# Pressure_Sensor_Platform.net
KiCad netlist of a schematic drawn in EAGLE
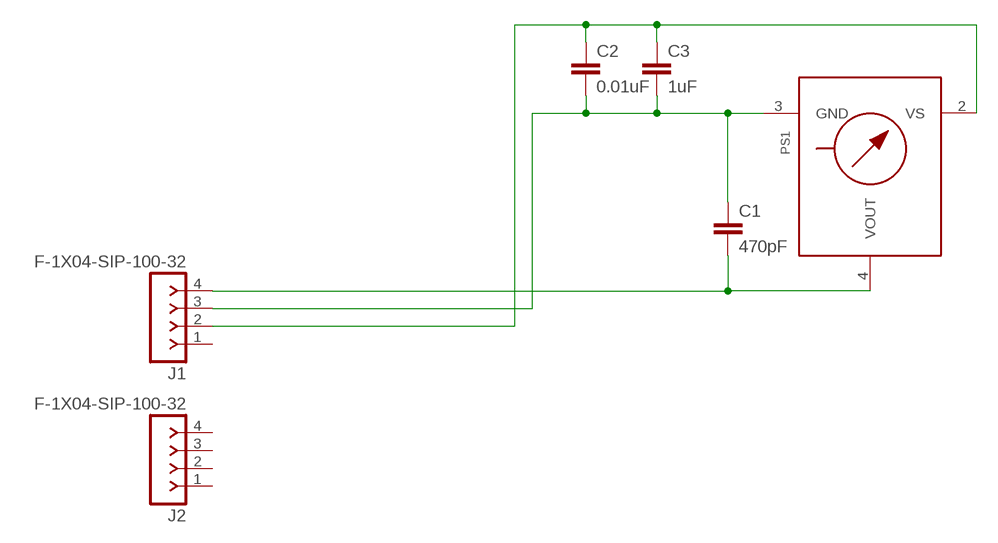
[diagram p0: schematic, sheet 1]

(export (version "E")
  (design (tool "Eeschema 10.0.6"))
  (components
    (comp (ref "C1")
      (value "470pF")
      (footprint "eagle-import:CAP-PTH-SMALL-KIT")
      (libsource (lib "eagle-import") (part "0.1UF-KIT-EZ-50V-20%"))
    )
    (comp (ref "C2")
      (value "0.01uF")
      (footprint "eagle-import:CAP-PTH-SMALL-KIT")
      (libsource (lib "eagle-import") (part "0.1UF-KIT-EZ-50V-20%"))
    )
    (comp (ref "C3")
      (value "1uF")
      (footprint "eagle-import:CAP-PTH-SMALL-KIT")
      (libsource (lib "eagle-import") (part "0.1UF-KIT-EZ-50V-20%"))
    )
    (comp (ref "J1")
      (value "F-1X04-SIP-100-32")
      (footprint "eagle-import:SIP-100-04-32")
      (libsource (lib "eagle-import") (part "F-1X04-SIP-100-32"))
    )
    (comp (ref "J2")
      (value "F-1X04-SIP-100-32")
      (footprint "eagle-import:SIP-100-04-32")
      (libsource (lib "eagle-import") (part "F-1X04-SIP-100-32"))
    )
    (comp (ref "PS1")
      (value "MPX-1351")
      (footprint "eagle-import:1351")
      (libsource (lib "eagle-import") (part "MPX-1351"))
    )
  )
  (nets
    (net (code "1") (name "Net-(PS1-GND)") (class "Default")
      (node (ref "C1") (pin "1") (pinfunction "1_1") (pintype "passive"))
      (node (ref "C2") (pin "2") (pinfunction "2_2") (pintype "passive"))
      (node (ref "C3") (pin "2") (pinfunction "2_2") (pintype "passive"))
      (node (ref "J1") (pin "3") (pinfunction "3_3") (pintype "passive"))
      (node (ref "PS1") (pin "3") (pinfunction "GND_3") (pintype "power_in"))
    )
    (net (code "2") (name "Net-(PS1-VOUT)") (class "Default")
      (node (ref "C1") (pin "2") (pinfunction "2_2") (pintype "passive"))
      (node (ref "J1") (pin "4") (pinfunction "4_4") (pintype "passive"))
      (node (ref "PS1") (pin "4") (pinfunction "VOUT_4") (pintype "output"))
    )
    (net (code "3") (name "Net-(PS1-VS)") (class "Default")
      (node (ref "C2") (pin "1") (pinfunction "1_1") (pintype "passive"))
      (node (ref "C3") (pin "1") (pinfunction "1_1") (pintype "passive"))
      (node (ref "J1") (pin "2") (pinfunction "2_2") (pintype "passive"))
      (node (ref "PS1") (pin "2") (pinfunction "VS_2") (pintype "power_in"))
    )
    (net (code "4") (name "unconnected-(J1-Pad1)") (class "Default")
      (node (ref "J1") (pin "1") (pinfunction "1_1") (pintype "passive"))
    )
    (net (code "5") (name "unconnected-(J2-Pad1)") (class "Default")
      (node (ref "J2") (pin "1") (pinfunction "1_1") (pintype "passive"))
    )
    (net (code "6") (name "unconnected-(J2-Pad2)") (class "Default")
      (node (ref "J2") (pin "2") (pinfunction "2_2") (pintype "passive"))
    )
    (net (code "7") (name "unconnected-(J2-Pad3)") (class "Default")
      (node (ref "J2") (pin "3") (pinfunction "3_3") (pintype "passive"))
    )
    (net (code "8") (name "unconnected-(J2-Pad4)") (class "Default")
      (node (ref "J2") (pin "4") (pinfunction "4_4") (pintype "passive"))
    )
    (net (code "9") (name "unconnected-(PS1-NC-Pad1)") (class "Default")
      (node (ref "PS1") (pin "1") (pinfunction "NC_1") (pintype "no_connect"))
    )
    (net (code "10") (name "unconnected-(PS1-NC-Pad5)") (class "Default")
      (node (ref "PS1") (pin "5") (pinfunction "NC_5") (pintype "no_connect"))
    )
    (net (code "11") (name "unconnected-(PS1-NC-Pad6)") (class "Default")
      (node (ref "PS1") (pin "6") (pinfunction "NC_6") (pintype "no_connect"))
    )
  )
)
